# CSX_Capsense.net
KiCad netlist of a schematic drawn in Altium Designer
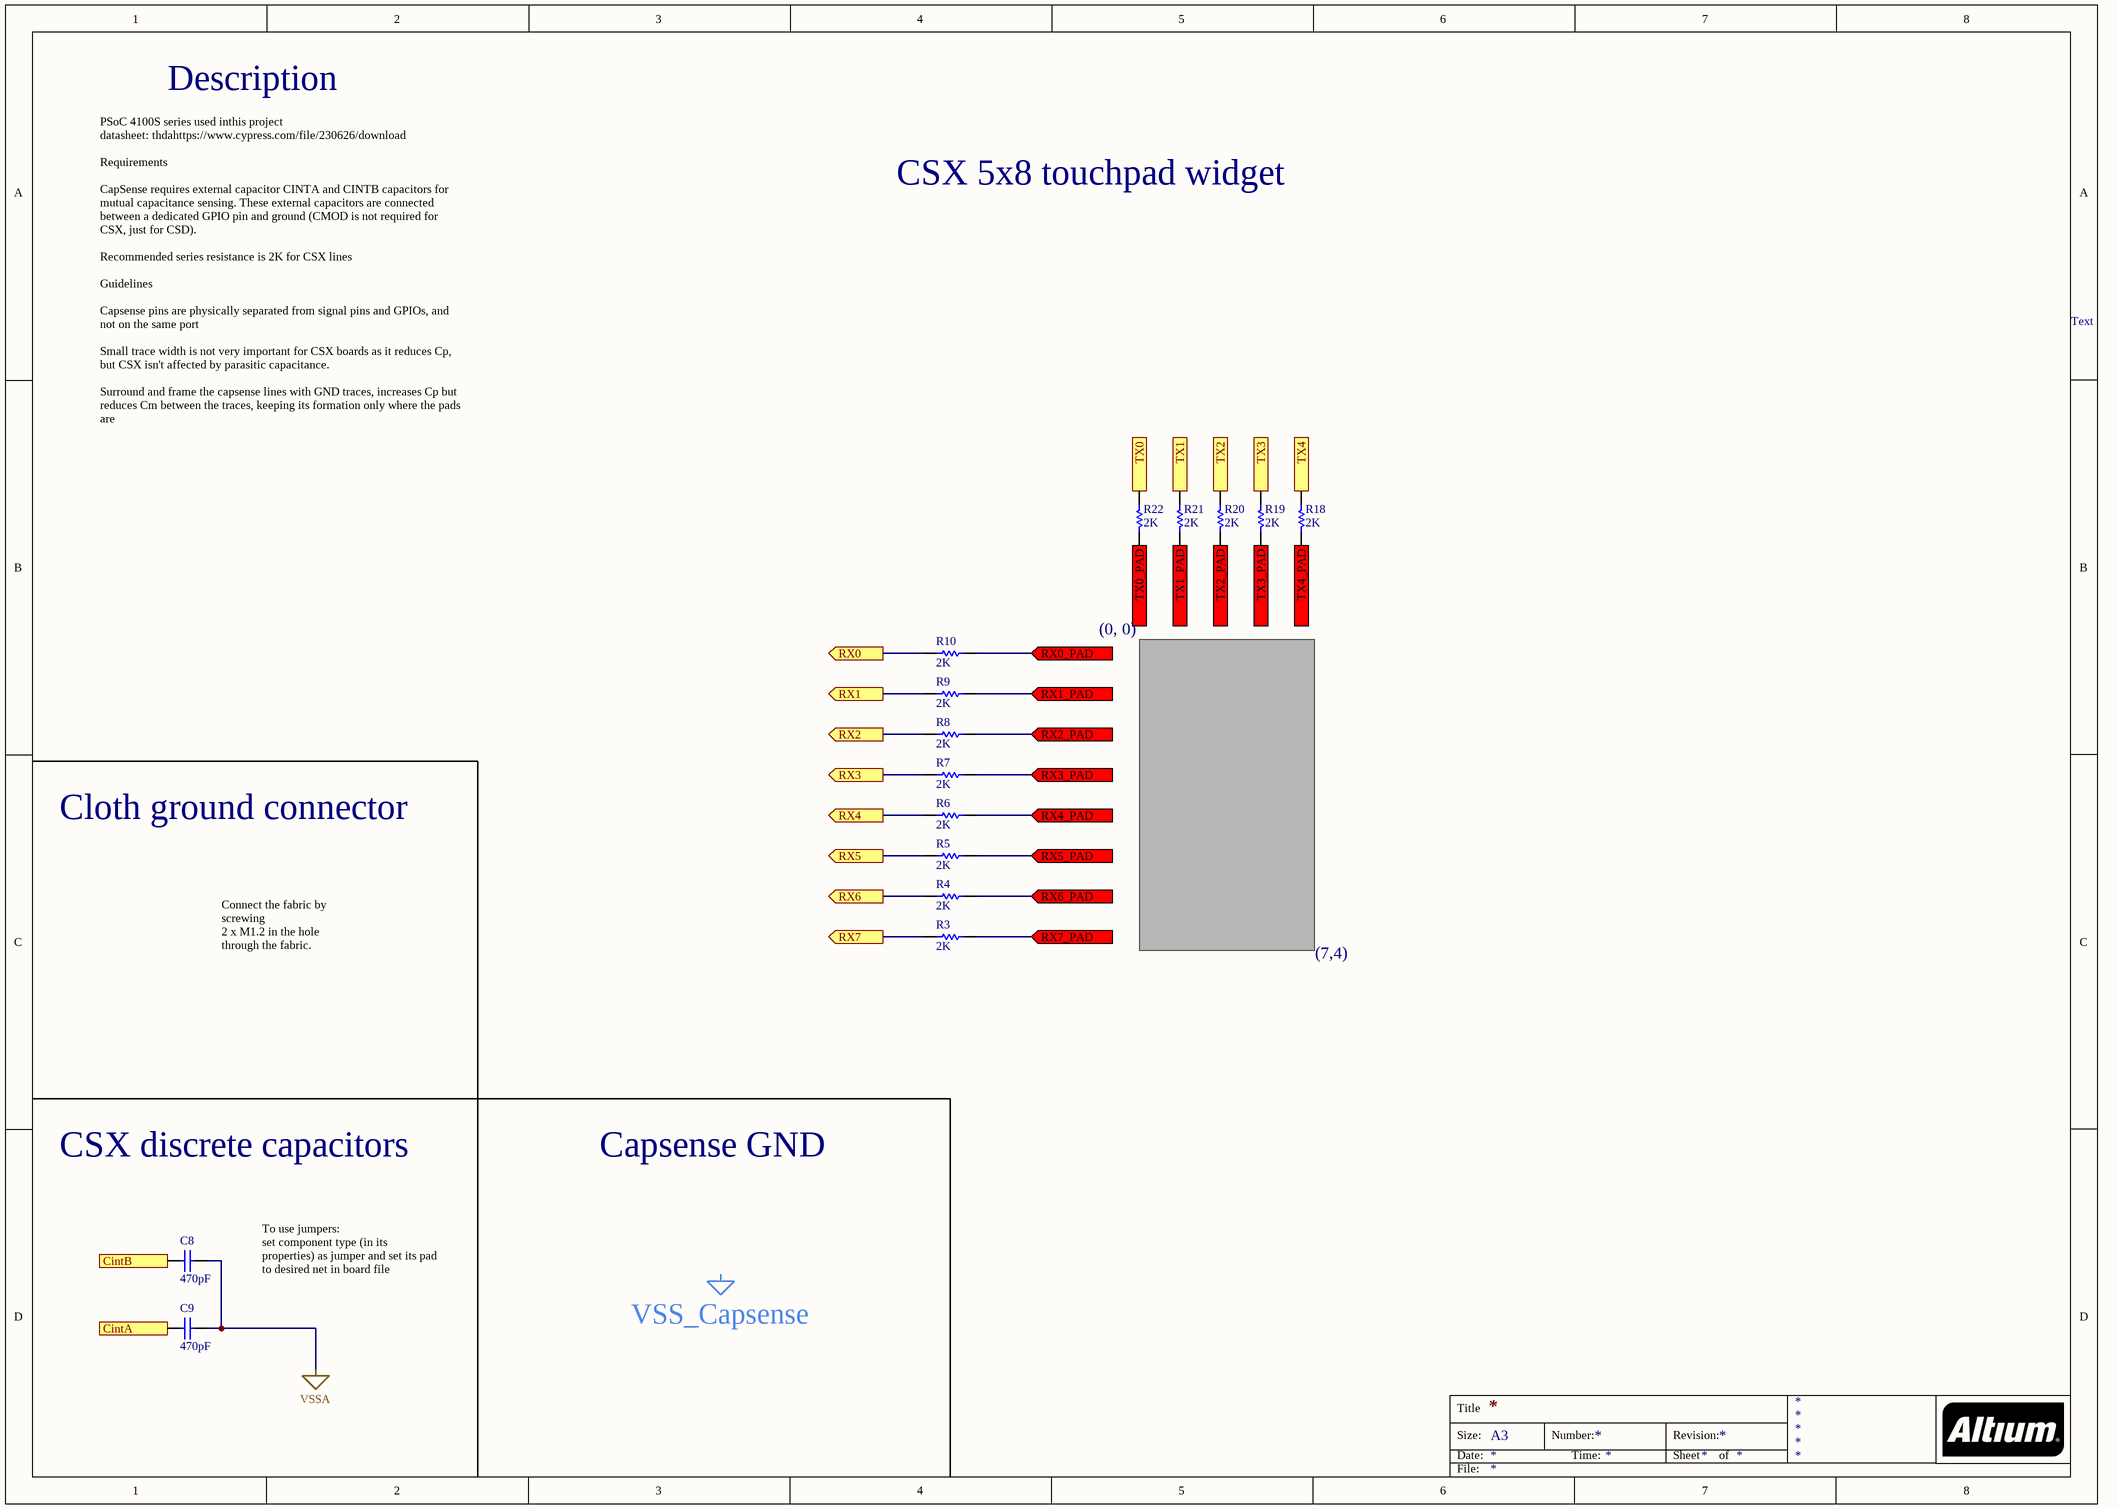
[diagram p0: CSX_Capsense.SchDoc]

(export (version "E")
  (design (tool "Eeschema 10.0.6"))
  (components
    (comp (ref "C8")
      (value "470pF")
      (footprint "CAPC0603(1608)100_N")
      (description "CAP 470pF 10V ±10% 0603 (1608 Metric) Thickness 1mm SMD")
      (fields (field (name "TOLERANCE") "Â±10%"))
      (libsource (lib "Altium Content Vault") (part "CAP"))
    )
    (comp (ref "C9")
      (value "470pF")
      (footprint "CAPC0603(1608)100_N")
      (description "CAP 470pF 10V ±10% 0603 (1608 Metric) Thickness 1mm SMD")
      (fields (field (name "TOLERANCE") "Â±10%"))
      (libsource (lib "Altium Content Vault") (part "CAP"))
    )
    (comp (ref "R3")
      (value "2K")
      (footprint "RESC0603(1608)_N")
      (description "2K 0.1W 5% 0603 (1608 Metric)  SMD")
      (fields (field (name "TOLERANCE") "5 %") (field (name "POWER") "0.1 W"))
      (libsource (lib "Altium Content Vault") (part "RES"))
    )
    (comp (ref "R4")
      (value "2K")
      (footprint "RESC0603(1608)_N")
      (description "2K 0.1W 5% 0603 (1608 Metric)  SMD")
      (fields (field (name "TOLERANCE") "5 %") (field (name "POWER") "0.1 W"))
      (libsource (lib "Altium Content Vault") (part "RES"))
    )
    (comp (ref "R5")
      (value "2K")
      (footprint "RESC0603(1608)_N")
      (description "2K 0.1W 5% 0603 (1608 Metric)  SMD")
      (fields (field (name "TOLERANCE") "5 %") (field (name "POWER") "0.1 W"))
      (libsource (lib "Altium Content Vault") (part "RES"))
    )
    (comp (ref "R6")
      (value "2K")
      (footprint "RESC0603(1608)_N")
      (description "2K 0.1W 5% 0603 (1608 Metric)  SMD")
      (fields (field (name "TOLERANCE") "5 %") (field (name "POWER") "0.1 W"))
      (libsource (lib "Altium Content Vault") (part "RES"))
    )
    (comp (ref "R7")
      (value "2K")
      (footprint "RESC0603(1608)_N")
      (description "2K 0.1W 5% 0603 (1608 Metric)  SMD")
      (fields (field (name "TOLERANCE") "5 %") (field (name "POWER") "0.1 W"))
      (libsource (lib "Altium Content Vault") (part "RES"))
    )
    (comp (ref "R8")
      (value "2K")
      (footprint "RESC0603(1608)_N")
      (description "2K 0.1W 5% 0603 (1608 Metric)  SMD")
      (fields (field (name "TOLERANCE") "5 %") (field (name "POWER") "0.1 W"))
      (libsource (lib "Altium Content Vault") (part "RES"))
    )
    (comp (ref "R9")
      (value "2K")
      (footprint "RESC0603(1608)_N")
      (description "2K 0.1W 5% 0603 (1608 Metric)  SMD")
      (fields (field (name "TOLERANCE") "5 %") (field (name "POWER") "0.1 W"))
      (libsource (lib "Altium Content Vault") (part "RES"))
    )
    (comp (ref "R10")
      (value "2K")
      (footprint "RESC0603(1608)_N")
      (description "2K 0.1W 5% 0603 (1608 Metric)  SMD")
      (fields (field (name "TOLERANCE") "5 %") (field (name "POWER") "0.1 W"))
      (libsource (lib "Altium Content Vault") (part "RES"))
    )
    (comp (ref "R18")
      (value "2K")
      (footprint "RESC0603(1608)_N")
      (description "2K 0.1W 5% 0603 (1608 Metric)  SMD")
      (fields (field (name "TOLERANCE") "5 %") (field (name "POWER") "0.1 W"))
      (libsource (lib "Altium Content Vault") (part "RES"))
    )
    (comp (ref "R19")
      (value "2K")
      (footprint "RESC0603(1608)_N")
      (description "2K 0.1W 5% 0603 (1608 Metric)  SMD")
      (fields (field (name "TOLERANCE") "5 %") (field (name "POWER") "0.1 W"))
      (libsource (lib "Altium Content Vault") (part "RES"))
    )
    (comp (ref "R20")
      (value "2K")
      (footprint "RESC0603(1608)_N")
      (description "2K 0.1W 5% 0603 (1608 Metric)  SMD")
      (fields (field (name "TOLERANCE") "5 %") (field (name "POWER") "0.1 W"))
      (libsource (lib "Altium Content Vault") (part "RES"))
    )
    (comp (ref "R21")
      (value "2K")
      (footprint "RESC0603(1608)_N")
      (description "2K 0.1W 5% 0603 (1608 Metric)  SMD")
      (fields (field (name "TOLERANCE") "5 %") (field (name "POWER") "0.1 W"))
      (libsource (lib "Altium Content Vault") (part "RES"))
    )
    (comp (ref "R22")
      (value "2K")
      (footprint "RESC0603(1608)_N")
      (description "2K 0.1W 5% 0603 (1608 Metric)  SMD")
      (fields (field (name "TOLERANCE") "5 %") (field (name "POWER") "0.1 W"))
      (libsource (lib "Altium Content Vault") (part "RES"))
    )
  )
  (nets
    (net (code "1") (name "/CintA") (class "Default")
      (node (ref "C9") (pin "1") (pinfunction "1_1") (pintype "passive"))
    )
    (net (code "2") (name "/CintB") (class "Default")
      (node (ref "C8") (pin "1") (pinfunction "1_1") (pintype "passive"))
    )
    (net (code "3") (name "/RX0") (class "Default")
      (node (ref "R10") (pin "1") (pinfunction "1_1") (pintype "passive"))
    )
    (net (code "4") (name "/RX0_PAD") (class "Default")
      (node (ref "R10") (pin "2") (pinfunction "2_2") (pintype "passive"))
    )
    (net (code "5") (name "/RX1") (class "Default")
      (node (ref "R9") (pin "1") (pinfunction "1_1") (pintype "passive"))
    )
    (net (code "6") (name "/RX1_PAD") (class "Default")
      (node (ref "R9") (pin "2") (pinfunction "2_2") (pintype "passive"))
    )
    (net (code "7") (name "/RX2") (class "Default")
      (node (ref "R8") (pin "1") (pinfunction "1_1") (pintype "passive"))
    )
    (net (code "8") (name "/RX2_PAD") (class "Default")
      (node (ref "R8") (pin "2") (pinfunction "2_2") (pintype "passive"))
    )
    (net (code "9") (name "/RX3") (class "Default")
      (node (ref "R7") (pin "1") (pinfunction "1_1") (pintype "passive"))
    )
    (net (code "10") (name "/RX3_PAD") (class "Default")
      (node (ref "R7") (pin "2") (pinfunction "2_2") (pintype "passive"))
    )
    (net (code "11") (name "/RX4") (class "Default")
      (node (ref "R6") (pin "1") (pinfunction "1_1") (pintype "passive"))
    )
    (net (code "12") (name "/RX4_PAD") (class "Default")
      (node (ref "R6") (pin "2") (pinfunction "2_2") (pintype "passive"))
    )
    (net (code "13") (name "/RX5") (class "Default")
      (node (ref "R5") (pin "1") (pinfunction "1_1") (pintype "passive"))
    )
    (net (code "14") (name "/RX5_PAD") (class "Default")
      (node (ref "R5") (pin "2") (pinfunction "2_2") (pintype "passive"))
    )
    (net (code "15") (name "/RX6") (class "Default")
      (node (ref "R4") (pin "1") (pinfunction "1_1") (pintype "passive"))
    )
    (net (code "16") (name "/RX6_PAD") (class "Default")
      (node (ref "R4") (pin "2") (pinfunction "2_2") (pintype "passive"))
    )
    (net (code "17") (name "/RX7") (class "Default")
      (node (ref "R3") (pin "1") (pinfunction "1_1") (pintype "passive"))
    )
    (net (code "18") (name "/RX7_PAD") (class "Default")
      (node (ref "R3") (pin "2") (pinfunction "2_2") (pintype "passive"))
    )
    (net (code "19") (name "/TX0") (class "Default")
      (node (ref "R22") (pin "1") (pinfunction "1_1") (pintype "passive"))
    )
    (net (code "20") (name "/TX0_PAD") (class "Default")
      (node (ref "R22") (pin "2") (pinfunction "2_2") (pintype "passive"))
    )
    (net (code "21") (name "/TX1") (class "Default")
      (node (ref "R21") (pin "1") (pinfunction "1_1") (pintype "passive"))
    )
    (net (code "22") (name "/TX1_PAD") (class "Default")
      (node (ref "R21") (pin "2") (pinfunction "2_2") (pintype "passive"))
    )
    (net (code "23") (name "/TX2") (class "Default")
      (node (ref "R20") (pin "1") (pinfunction "1_1") (pintype "passive"))
    )
    (net (code "24") (name "/TX2_PAD") (class "Default")
      (node (ref "R20") (pin "2") (pinfunction "2_2") (pintype "passive"))
    )
    (net (code "25") (name "/TX3") (class "Default")
      (node (ref "R19") (pin "1") (pinfunction "1_1") (pintype "passive"))
    )
    (net (code "26") (name "/TX3_PAD") (class "Default")
      (node (ref "R19") (pin "2") (pinfunction "2_2") (pintype "passive"))
    )
    (net (code "27") (name "/TX4") (class "Default")
      (node (ref "R18") (pin "1") (pinfunction "1_1") (pintype "passive"))
    )
    (net (code "28") (name "/TX4_PAD") (class "Default")
      (node (ref "R18") (pin "2") (pinfunction "2_2") (pintype "passive"))
    )
    (net (code "29") (name "VSSA") (class "Default")
      (node (ref "C8") (pin "2") (pinfunction "2_2") (pintype "passive"))
      (node (ref "C9") (pin "2") (pinfunction "2_2") (pintype "passive"))
    )
  )
)
